# SMD_RGB_Breakout.net
KiCad netlist of a schematic drawn in EAGLE
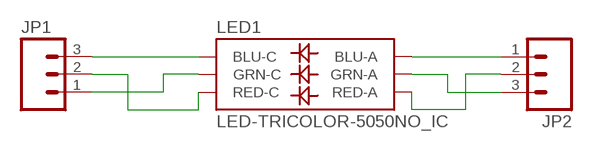
[diagram p0: schematic, sheet 1]

(export (version "E")
  (design (tool "Eeschema 10.0.6"))
  (components
    (comp (ref "JP1")
      (value "M03PTH")
      (footprint "eagle-import:1X03")
      (libsource (lib "eagle-import") (part "M03PTH"))
    )
    (comp (ref "JP2")
      (value "M03PTH")
      (footprint "eagle-import:1X03")
      (libsource (lib "eagle-import") (part "M03PTH"))
    )
    (comp (ref "LED1")
      (value "LED-TRICOLOR-5050NO_IC")
      (footprint "eagle-import:LED-TRICOLOR-5050")
      (libsource (lib "eagle-import") (part "LED-TRICOLOR-5050NO_IC"))
    )
  )
  (nets
    (net (code "1") (name "Net-(LED1-BLU-A)") (class "Default")
      (node (ref "JP2") (pin "1") (pinfunction "1_1") (pintype "passive"))
      (node (ref "LED1") (pin "3") (pinfunction "BLU-A_3") (pintype "bidirectional"))
    )
    (net (code "2") (name "Net-(LED1-BLU-C)") (class "Default")
      (node (ref "JP1") (pin "3") (pinfunction "3_3") (pintype "passive"))
      (node (ref "LED1") (pin "4") (pinfunction "BLU-C_4") (pintype "bidirectional"))
    )
    (net (code "3") (name "Net-(LED1-GRN-A)") (class "Default")
      (node (ref "JP2") (pin "3") (pinfunction "3_3") (pintype "passive"))
      (node (ref "LED1") (pin "1") (pinfunction "GRN-A_1") (pintype "bidirectional"))
    )
    (net (code "4") (name "Net-(LED1-GRN-C)") (class "Default")
      (node (ref "JP1") (pin "1") (pinfunction "1_1") (pintype "passive"))
      (node (ref "LED1") (pin "6") (pinfunction "GRN-C_6") (pintype "bidirectional"))
    )
    (net (code "5") (name "Net-(LED1-RED-A)") (class "Default")
      (node (ref "JP2") (pin "2") (pinfunction "2_2") (pintype "passive"))
      (node (ref "LED1") (pin "2") (pinfunction "RED-A_2") (pintype "bidirectional"))
    )
    (net (code "6") (name "Net-(LED1-RED-C)") (class "Default")
      (node (ref "JP1") (pin "2") (pinfunction "2_2") (pintype "passive"))
      (node (ref "LED1") (pin "5") (pinfunction "RED-C_5") (pintype "bidirectional"))
    )
  )
)
